# OttoPi06a-RPi3AHAT.net
KiCad netlist of a schematic drawn in EAGLE
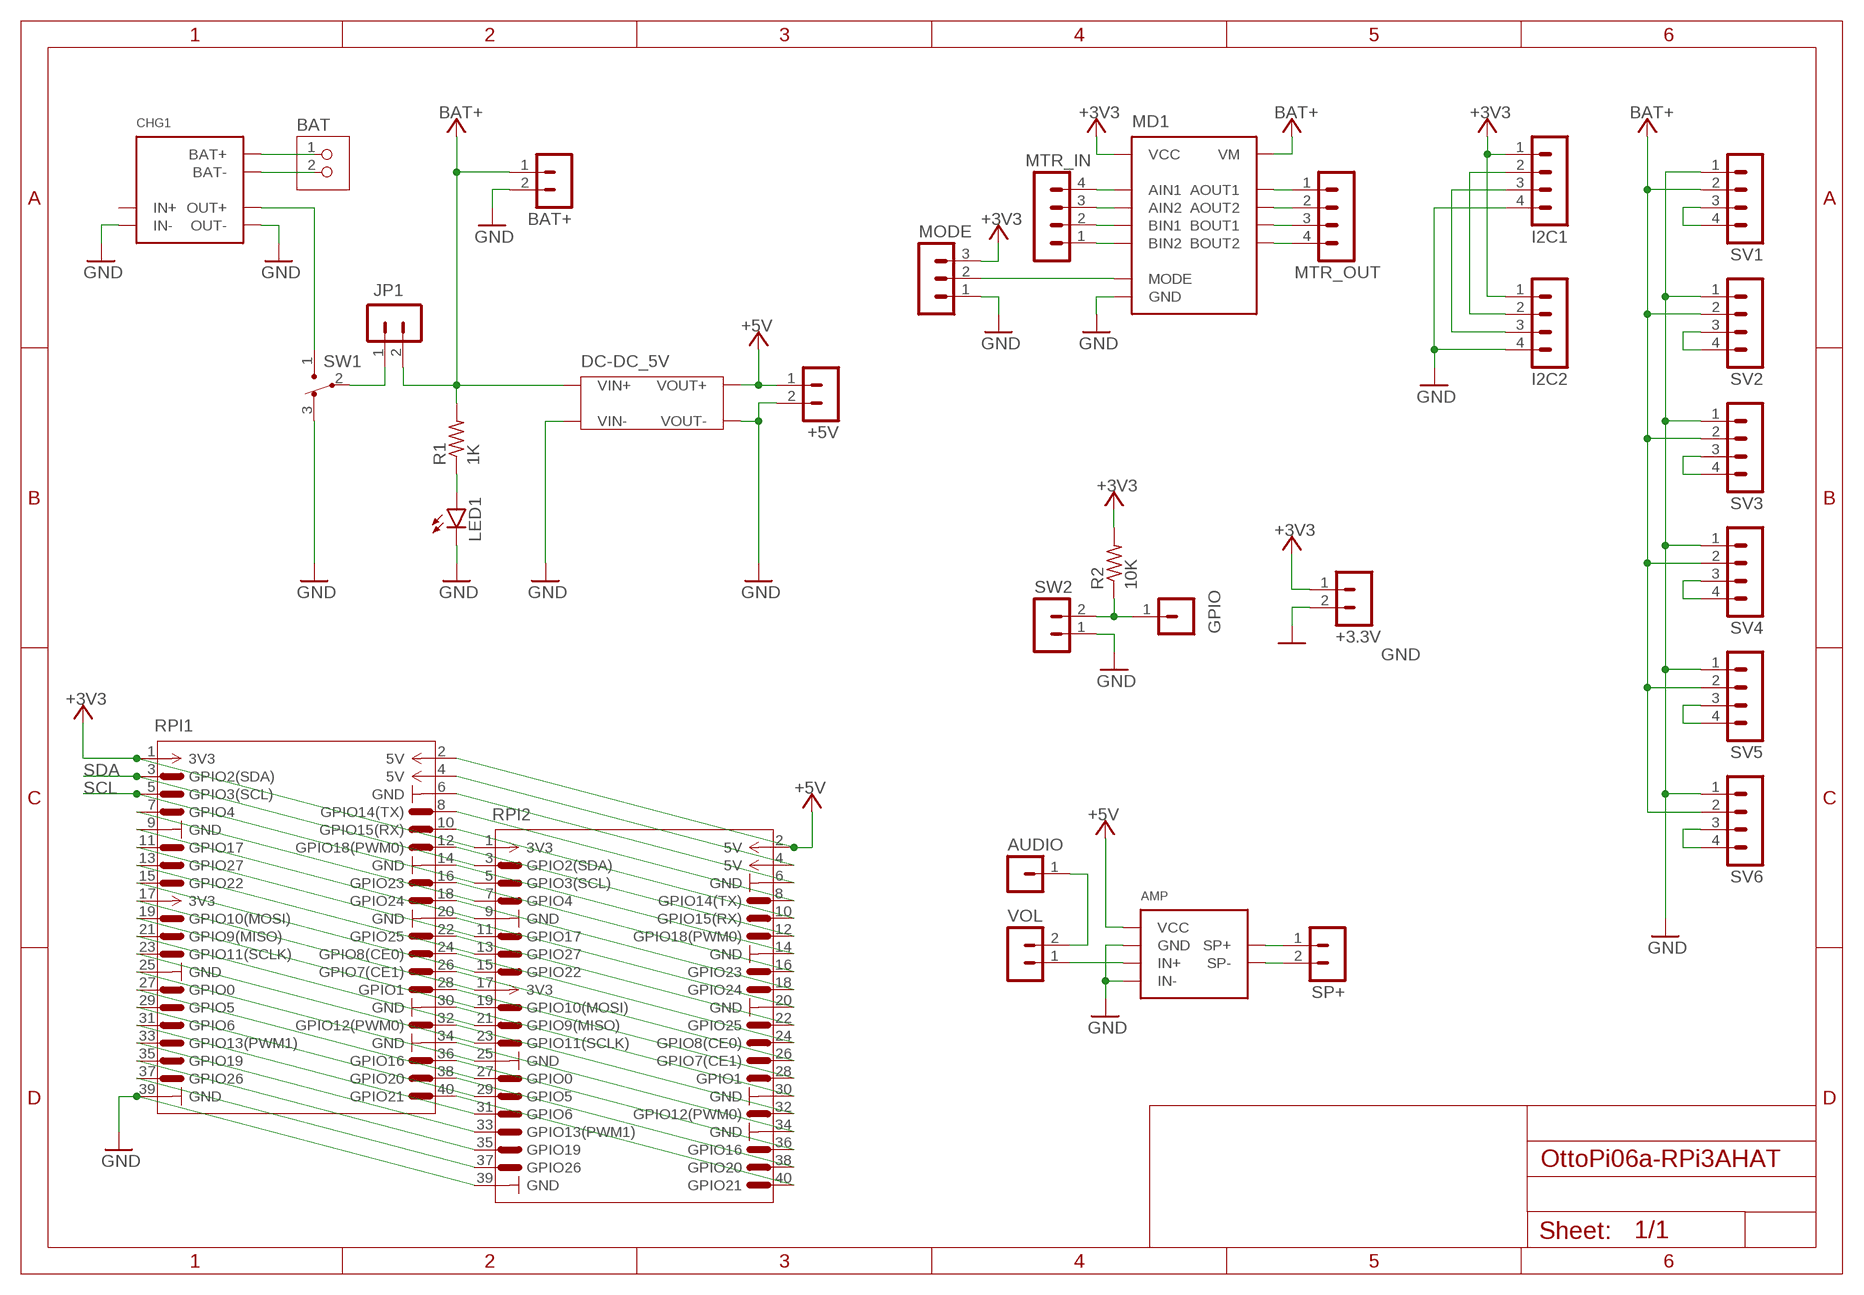
[diagram p0: schematic, sheet 1]

(export (version "E")
  (design (tool "Eeschema 10.0.6"))
  (components
    (comp (ref "+3.3V")
      (value "MA02-1")
      (footprint "eagle-import:MA02-1")
      (libsource (lib "eagle-import") (part "MA02-1"))
    )
    (comp (ref "+5V")
      (value "MA02-1")
      (footprint "eagle-import:MA02-1")
      (libsource (lib "eagle-import") (part "MA02-1"))
    )
    (comp (ref "AMP")
      (value "PAM8012MOD")
      (footprint "eagle-import:PAM8012MOD-A")
      (libsource (lib "eagle-import") (part "PAM8012MOD"))
    )
    (comp (ref "AUDIO")
      (value "MA01-1")
      (footprint "eagle-import:MA01-1")
      (libsource (lib "eagle-import") (part "MA01-1"))
    )
    (comp (ref "BAT")
      (value "JST-PH2")
      (footprint "eagle-import:JST-PH2")
      (libsource (lib "eagle-import") (part "JST-PH2"))
    )
    (comp (ref "BAT+")
      (value "MA02-1")
      (footprint "eagle-import:MA02-1")
      (libsource (lib "eagle-import") (part "MA02-1"))
    )
    (comp (ref "CHG1")
      (value "TP4056MOD1")
      (footprint "eagle-import:TP4056MOD1")
      (libsource (lib "eagle-import") (part "TP4056MOD1"))
    )
    (comp (ref "DC-DC_5V")
      (value "DCDC-5V_28V-2A")
      (footprint "eagle-import:DCDC-5V_28V-2A")
      (libsource (lib "eagle-import") (part "DCDC-5V_28V-2A"))
    )
    (comp (ref "GPIO")
      (value "MA01-1")
      (footprint "eagle-import:MA01-1")
      (libsource (lib "eagle-import") (part "MA01-1"))
    )
    (comp (ref "I2C1")
      (value "MA04-1")
      (footprint "eagle-import:MA04-1")
      (libsource (lib "eagle-import") (part "MA04-1"))
    )
    (comp (ref "I2C2")
      (value "MA04-1")
      (footprint "eagle-import:MA04-1")
      (libsource (lib "eagle-import") (part "MA04-1"))
    )
    (comp (ref "JP1")
      (value "MA02-1")
      (footprint "eagle-import:MA02-1")
      (libsource (lib "eagle-import") (part "MA02-1"))
    )
    (comp (ref "LED1")
      (value "LED3MM")
      (footprint "eagle-import:LED3MM")
      (libsource (lib "eagle-import") (part "LED3MM"))
    )
    (comp (ref "MD1")
      (value "DRV8835MOD")
      (footprint "eagle-import:DRV8835MOD")
      (libsource (lib "eagle-import") (part "DRV8835MOD"))
    )
    (comp (ref "MODE")
      (value "MA03-1")
      (footprint "eagle-import:MA03-1")
      (libsource (lib "eagle-import") (part "MA03-1"))
    )
    (comp (ref "MTR_IN")
      (value "MA04-1")
      (footprint "eagle-import:MA04-1")
      (libsource (lib "eagle-import") (part "MA04-1"))
    )
    (comp (ref "MTR_OUT")
      (value "MA04-1")
      (footprint "eagle-import:MA04-1")
      (libsource (lib "eagle-import") (part "MA04-1"))
    )
    (comp (ref "R1")
      (value "1K")
      (footprint "eagle-import:0204_7")
      (libsource (lib "eagle-import") (part "R-US_0204/7"))
    )
    (comp (ref "R2")
      (value "10K")
      (footprint "eagle-import:0204_7")
      (libsource (lib "eagle-import") (part "R-US_0204/7"))
    )
    (comp (ref "RPI1")
      (value "RPI-PIN")
      (footprint "eagle-import:RPI-PIN")
      (libsource (lib "eagle-import") (part "RPI-PIN"))
    )
    (comp (ref "RPI2")
      (value "RPI-PIN")
      (footprint "eagle-import:RPI-PIN")
      (libsource (lib "eagle-import") (part "RPI-PIN"))
    )
    (comp (ref "SP+")
      (value "MA02-1")
      (footprint "eagle-import:MA02-1")
      (libsource (lib "eagle-import") (part "MA02-1"))
    )
    (comp (ref "SV1")
      (value "MA04-1")
      (footprint "eagle-import:MA04-1")
      (libsource (lib "eagle-import") (part "MA04-1"))
    )
    (comp (ref "SV2")
      (value "MA04-1")
      (footprint "eagle-import:MA04-1")
      (libsource (lib "eagle-import") (part "MA04-1"))
    )
    (comp (ref "SV3")
      (value "MA04-1")
      (footprint "eagle-import:MA04-1")
      (libsource (lib "eagle-import") (part "MA04-1"))
    )
    (comp (ref "SV4")
      (value "MA04-1")
      (footprint "eagle-import:MA04-1")
      (libsource (lib "eagle-import") (part "MA04-1"))
    )
    (comp (ref "SV5")
      (value "MA04-1")
      (footprint "eagle-import:MA04-1")
      (libsource (lib "eagle-import") (part "MA04-1"))
    )
    (comp (ref "SV6")
      (value "MA04-1")
      (footprint "eagle-import:MA04-1")
      (libsource (lib "eagle-import") (part "MA04-1"))
    )
    (comp (ref "SW1")
      (value "SW3-1")
      (footprint "eagle-import:SW3-1")
      (fields (field (name "MF") "HiLetgo"))
      (libsource (lib "eagle-import") (part "SW3-1"))
    )
    (comp (ref "SW2")
      (value "MA02-1")
      (footprint "eagle-import:MA02-1")
      (libsource (lib "eagle-import") (part "MA02-1"))
    )
    (comp (ref "VOL")
      (value "MA02-1")
      (footprint "eagle-import:MA02-1")
      (libsource (lib "eagle-import") (part "MA02-1"))
    )
  )
  (nets
    (net (code "1") (name "+3V3") (class "Default")
      (node (ref "+3.3V") (pin "1") (pinfunction "1_1") (pintype "passive"))
      (node (ref "I2C1") (pin "1") (pinfunction "1_1") (pintype "passive"))
      (node (ref "I2C2") (pin "1") (pinfunction "1_1") (pintype "passive"))
      (node (ref "MD1") (pin "VCC") (pinfunction "VCC_VCC") (pintype "input"))
      (node (ref "MODE") (pin "3") (pinfunction "3_3") (pintype "passive"))
      (node (ref "R2") (pin "2") (pinfunction "2_2") (pintype "passive"))
      (node (ref "RPI1") (pin "1") (pinfunction "3V3_1") (pintype "passive"))
      (node (ref "RPI2") (pin "1") (pinfunction "3V3_1") (pintype "passive"))
    )
    (net (code "2") (name "+5V") (class "Default")
      (node (ref "+5V") (pin "1") (pinfunction "1_1") (pintype "passive"))
      (node (ref "AMP") (pin "V+") (pinfunction "VCC_V+") (pintype "passive"))
      (node (ref "DC-DC_5V") (pin "VOUT+") (pinfunction "VOUT+_VOUT+") (pintype "power_in"))
      (node (ref "RPI1") (pin "2") (pinfunction "5V_2") (pintype "passive"))
      (node (ref "RPI2") (pin "2") (pinfunction "5V_2") (pintype "passive"))
    )
    (net (code "3") (name "/SCL") (class "Default")
      (node (ref "I2C1") (pin "3") (pinfunction "3_3") (pintype "passive"))
      (node (ref "I2C2") (pin "3") (pinfunction "3_3") (pintype "passive"))
      (node (ref "RPI1") (pin "5") (pinfunction "GPIO3(SCL)_5") (pintype "passive"))
      (node (ref "RPI2") (pin "5") (pinfunction "GPIO3(SCL)_5") (pintype "passive"))
    )
    (net (code "4") (name "/SDA") (class "Default")
      (node (ref "I2C1") (pin "2") (pinfunction "2_2") (pintype "passive"))
      (node (ref "I2C2") (pin "2") (pinfunction "2_2") (pintype "passive"))
      (node (ref "RPI1") (pin "3") (pinfunction "GPIO2(SDA)_3") (pintype "passive"))
      (node (ref "RPI2") (pin "3") (pinfunction "GPIO2(SDA)_3") (pintype "passive"))
    )
    (net (code "5") (name "BAT+") (class "Default")
      (node (ref "BAT+") (pin "1") (pinfunction "1_1") (pintype "passive"))
      (node (ref "DC-DC_5V") (pin "VIN+") (pinfunction "VIN+_VIN+") (pintype "power_in"))
      (node (ref "JP1") (pin "2") (pinfunction "2_2") (pintype "passive"))
      (node (ref "MD1") (pin "VM") (pinfunction "VM_VM") (pintype "input"))
      (node (ref "R1") (pin "2") (pinfunction "2_2") (pintype "passive"))
      (node (ref "SV1") (pin "2") (pinfunction "2_2") (pintype "passive"))
      (node (ref "SV2") (pin "2") (pinfunction "2_2") (pintype "passive"))
      (node (ref "SV3") (pin "2") (pinfunction "2_2") (pintype "passive"))
      (node (ref "SV4") (pin "2") (pinfunction "2_2") (pintype "passive"))
      (node (ref "SV5") (pin "2") (pinfunction "2_2") (pintype "passive"))
      (node (ref "SV6") (pin "2") (pinfunction "2_2") (pintype "passive"))
    )
    (net (code "6") (name "GND") (class "Default")
      (node (ref "+3.3V") (pin "2") (pinfunction "2_2") (pintype "passive"))
      (node (ref "+5V") (pin "2") (pinfunction "2_2") (pintype "passive"))
      (node (ref "AMP") (pin "GND") (pinfunction "GND_GND") (pintype "passive"))
      (node (ref "AMP") (pin "IN-") (pinfunction "IN-_IN-") (pintype "input"))
      (node (ref "BAT+") (pin "2") (pinfunction "2_2") (pintype "passive"))
      (node (ref "CHG1") (pin "IN-") (pinfunction "IN-_IN-") (pintype "passive"))
      (node (ref "CHG1") (pin "OUT-") (pinfunction "OUT-_OUT-") (pintype "passive"))
      (node (ref "DC-DC_5V") (pin "VIN-") (pinfunction "VIN-_VIN-") (pintype "power_in"))
      (node (ref "DC-DC_5V") (pin "VOUT-") (pinfunction "VOUT-_VOUT-") (pintype "power_in"))
      (node (ref "I2C1") (pin "4") (pinfunction "4_4") (pintype "passive"))
      (node (ref "I2C2") (pin "4") (pinfunction "4_4") (pintype "passive"))
      (node (ref "LED1") (pin "K") (pinfunction "C_K") (pintype "passive"))
      (node (ref "MD1") (pin "GND") (pinfunction "GND_GND") (pintype "power_in"))
      (node (ref "MODE") (pin "1") (pinfunction "1_1") (pintype "passive"))
      (node (ref "RPI1") (pin "39") (pinfunction "GND_39") (pintype "passive"))
      (node (ref "RPI2") (pin "39") (pinfunction "GND_39") (pintype "passive"))
      (node (ref "SV1") (pin "1") (pinfunction "1_1") (pintype "passive"))
      (node (ref "SV2") (pin "1") (pinfunction "1_1") (pintype "passive"))
      (node (ref "SV3") (pin "1") (pinfunction "1_1") (pintype "passive"))
      (node (ref "SV4") (pin "1") (pinfunction "1_1") (pintype "passive"))
      (node (ref "SV5") (pin "1") (pinfunction "1_1") (pintype "passive"))
      (node (ref "SV6") (pin "1") (pinfunction "1_1") (pintype "passive"))
      (node (ref "SW1") (pin "3") (pinfunction "3_3") (pintype "passive"))
      (node (ref "SW2") (pin "1") (pinfunction "1_1") (pintype "passive"))
    )
    (net (code "7") (name "Net-(AMP-PadIN+)") (class "Default")
      (node (ref "AMP") (pin "IN+") (pinfunction "IN+_IN+") (pintype "input"))
      (node (ref "VOL") (pin "1") (pinfunction "1_1") (pintype "passive"))
    )
    (net (code "8") (name "Net-(AMP-SP+)") (class "Default")
      (node (ref "AMP") (pin "SP+@1") (pinfunction "SP+_SP+@1") (pintype "output"))
      (node (ref "SP+") (pin "1") (pinfunction "1_1") (pintype "passive"))
    )
    (net (code "9") (name "Net-(AMP-SP-)") (class "Default")
      (node (ref "AMP") (pin "SP-@1") (pinfunction "SP-_SP-@1") (pintype "output"))
      (node (ref "SP+") (pin "2") (pinfunction "2_2") (pintype "passive"))
    )
    (net (code "10") (name "Net-(AUDIO-Pad1)") (class "Default")
      (node (ref "AUDIO") (pin "1") (pinfunction "1_1") (pintype "passive"))
      (node (ref "VOL") (pin "2") (pinfunction "2_2") (pintype "passive"))
    )
    (net (code "11") (name "Net-(BAT-Pad1)") (class "Default")
      (node (ref "BAT") (pin "1") (pinfunction "1_1") (pintype "passive"))
      (node (ref "CHG1") (pin "BAT+") (pinfunction "BAT+_BAT+") (pintype "passive"))
    )
    (net (code "12") (name "Net-(BAT-Pad2)") (class "Default")
      (node (ref "BAT") (pin "2") (pinfunction "2_2") (pintype "passive"))
      (node (ref "CHG1") (pin "BAT-") (pinfunction "BAT-_BAT-") (pintype "passive"))
    )
    (net (code "13") (name "Net-(CHG1-PadOUT+)") (class "Default")
      (node (ref "CHG1") (pin "OUT+") (pinfunction "OUT+_OUT+") (pintype "passive"))
      (node (ref "SW1") (pin "1") (pinfunction "1_1") (pintype "passive"))
    )
    (net (code "14") (name "Net-(GPIO-Pad1)") (class "Default")
      (node (ref "GPIO") (pin "1") (pinfunction "1_1") (pintype "passive"))
      (node (ref "R2") (pin "1") (pinfunction "1_1") (pintype "passive"))
      (node (ref "SW2") (pin "2") (pinfunction "2_2") (pintype "passive"))
    )
    (net (code "15") (name "Net-(JP1-Pad1)") (class "Default")
      (node (ref "JP1") (pin "1") (pinfunction "1_1") (pintype "passive"))
      (node (ref "SW1") (pin "2") (pinfunction "2_2") (pintype "passive"))
    )
    (net (code "16") (name "Net-(LED1-PadA)") (class "Default")
      (node (ref "LED1") (pin "A") (pinfunction "A_A") (pintype "passive"))
      (node (ref "R1") (pin "1") (pinfunction "1_1") (pintype "passive"))
    )
    (net (code "17") (name "Net-(MD1-PadAIN1)") (class "Default")
      (node (ref "MD1") (pin "AIN1") (pinfunction "AIN1_AIN1") (pintype "input"))
      (node (ref "MTR_IN") (pin "4") (pinfunction "4_4") (pintype "passive"))
    )
    (net (code "18") (name "Net-(MD1-PadAIN2)") (class "Default")
      (node (ref "MD1") (pin "AIN2") (pinfunction "AIN2_AIN2") (pintype "input"))
      (node (ref "MTR_IN") (pin "3") (pinfunction "3_3") (pintype "passive"))
    )
    (net (code "19") (name "Net-(MD1-PadAOUT1)") (class "Default")
      (node (ref "MD1") (pin "AOUT1") (pinfunction "AOUT1_AOUT1") (pintype "output"))
      (node (ref "MTR_OUT") (pin "1") (pinfunction "1_1") (pintype "passive"))
    )
    (net (code "20") (name "Net-(MD1-PadAOUT2)") (class "Default")
      (node (ref "MD1") (pin "AOUT2") (pinfunction "AOUT2_AOUT2") (pintype "output"))
      (node (ref "MTR_OUT") (pin "2") (pinfunction "2_2") (pintype "passive"))
    )
    (net (code "21") (name "Net-(MD1-PadBIN1)") (class "Default")
      (node (ref "MD1") (pin "BIN1") (pinfunction "BIN1_BIN1") (pintype "input"))
      (node (ref "MTR_IN") (pin "2") (pinfunction "2_2") (pintype "passive"))
    )
    (net (code "22") (name "Net-(MD1-PadBIN2)") (class "Default")
      (node (ref "MD1") (pin "BIN2") (pinfunction "BIN2_BIN2") (pintype "input"))
      (node (ref "MTR_IN") (pin "1") (pinfunction "1_1") (pintype "passive"))
    )
    (net (code "23") (name "Net-(MD1-PadBOUT1)") (class "Default")
      (node (ref "MD1") (pin "BOUT1") (pinfunction "BOUT1_BOUT1") (pintype "output"))
      (node (ref "MTR_OUT") (pin "3") (pinfunction "3_3") (pintype "passive"))
    )
    (net (code "24") (name "Net-(MD1-PadBOUT2)") (class "Default")
      (node (ref "MD1") (pin "BOUT2") (pinfunction "BOUT2_BOUT2") (pintype "output"))
      (node (ref "MTR_OUT") (pin "4") (pinfunction "4_4") (pintype "passive"))
    )
    (net (code "25") (name "Net-(MD1-PadMODE)") (class "Default")
      (node (ref "MD1") (pin "MODE") (pinfunction "MODE_MODE") (pintype "input"))
      (node (ref "MODE") (pin "2") (pinfunction "2_2") (pintype "passive"))
    )
    (net (code "26") (name "Net-(RPI1-3V3-Pad17)") (class "Default")
      (node (ref "RPI1") (pin "17") (pinfunction "3V3_17") (pintype "passive"))
      (node (ref "RPI2") (pin "17") (pinfunction "3V3_17") (pintype "passive"))
    )
    (net (code "27") (name "Net-(RPI1-5V-Pad4)") (class "Default")
      (node (ref "RPI1") (pin "4") (pinfunction "5V_4") (pintype "passive"))
      (node (ref "RPI2") (pin "4") (pinfunction "5V_4") (pintype "passive"))
    )
    (net (code "28") (name "Net-(RPI1-GND-Pad6)") (class "Default")
      (node (ref "RPI1") (pin "6") (pinfunction "GND_6") (pintype "passive"))
      (node (ref "RPI2") (pin "6") (pinfunction "GND_6") (pintype "passive"))
    )
    (net (code "29") (name "Net-(RPI1-GND-Pad9)") (class "Default")
      (node (ref "RPI1") (pin "9") (pinfunction "GND_9") (pintype "passive"))
      (node (ref "RPI2") (pin "9") (pinfunction "GND_9") (pintype "passive"))
    )
    (net (code "30") (name "Net-(RPI1-GND-Pad14)") (class "Default")
      (node (ref "RPI1") (pin "14") (pinfunction "GND_14") (pintype "passive"))
      (node (ref "RPI2") (pin "14") (pinfunction "GND_14") (pintype "passive"))
    )
    (net (code "31") (name "Net-(RPI1-GND-Pad20)") (class "Default")
      (node (ref "RPI1") (pin "20") (pinfunction "GND_20") (pintype "passive"))
      (node (ref "RPI2") (pin "20") (pinfunction "GND_20") (pintype "passive"))
    )
    (net (code "32") (name "Net-(RPI1-GND-Pad25)") (class "Default")
      (node (ref "RPI1") (pin "25") (pinfunction "GND_25") (pintype "passive"))
      (node (ref "RPI2") (pin "25") (pinfunction "GND_25") (pintype "passive"))
    )
    (net (code "33") (name "Net-(RPI1-GND-Pad30)") (class "Default")
      (node (ref "RPI1") (pin "30") (pinfunction "GND_30") (pintype "passive"))
      (node (ref "RPI2") (pin "30") (pinfunction "GND_30") (pintype "passive"))
    )
    (net (code "34") (name "Net-(RPI1-GND-Pad34)") (class "Default")
      (node (ref "RPI1") (pin "34") (pinfunction "GND_34") (pintype "passive"))
      (node (ref "RPI2") (pin "34") (pinfunction "GND_34") (pintype "passive"))
    )
    (net (code "35") (name "Net-(RPI1-GPIO0)") (class "Default")
      (node (ref "RPI1") (pin "27") (pinfunction "GPIO0_27") (pintype "passive"))
      (node (ref "RPI2") (pin "27") (pinfunction "GPIO0_27") (pintype "passive"))
    )
    (net (code "36") (name "Net-(RPI1-GPIO1)") (class "Default")
      (node (ref "RPI1") (pin "28") (pinfunction "GPIO1_28") (pintype "passive"))
      (node (ref "RPI2") (pin "28") (pinfunction "GPIO1_28") (pintype "passive"))
    )
    (net (code "37") (name "Net-(RPI1-GPIO4)") (class "Default")
      (node (ref "RPI1") (pin "7") (pinfunction "GPIO4_7") (pintype "passive"))
      (node (ref "RPI2") (pin "7") (pinfunction "GPIO4_7") (pintype "passive"))
    )
    (net (code "38") (name "Net-(RPI1-GPIO5)") (class "Default")
      (node (ref "RPI1") (pin "29") (pinfunction "GPIO5_29") (pintype "passive"))
      (node (ref "RPI2") (pin "29") (pinfunction "GPIO5_29") (pintype "passive"))
    )
    (net (code "39") (name "Net-(RPI1-GPIO6)") (class "Default")
      (node (ref "RPI1") (pin "31") (pinfunction "GPIO6_31") (pintype "passive"))
      (node (ref "RPI2") (pin "31") (pinfunction "GPIO6_31") (pintype "passive"))
    )
    (net (code "40") (name "Net-(RPI1-GPIO7(CE1))") (class "Default")
      (node (ref "RPI1") (pin "26") (pinfunction "GPIO7(CE1)_26") (pintype "passive"))
      (node (ref "RPI2") (pin "26") (pinfunction "GPIO7(CE1)_26") (pintype "passive"))
    )
    (net (code "41") (name "Net-(RPI1-GPIO8(CE0))") (class "Default")
      (node (ref "RPI1") (pin "24") (pinfunction "GPIO8(CE0)_24") (pintype "passive"))
      (node (ref "RPI2") (pin "24") (pinfunction "GPIO8(CE0)_24") (pintype "passive"))
    )
    (net (code "42") (name "Net-(RPI1-GPIO9(MISO))") (class "Default")
      (node (ref "RPI1") (pin "21") (pinfunction "GPIO9(MISO)_21") (pintype "passive"))
      (node (ref "RPI2") (pin "21") (pinfunction "GPIO9(MISO)_21") (pintype "passive"))
    )
    (net (code "43") (name "Net-(RPI1-GPIO10(MOSI))") (class "Default")
      (node (ref "RPI1") (pin "19") (pinfunction "GPIO10(MOSI)_19") (pintype "passive"))
      (node (ref "RPI2") (pin "19") (pinfunction "GPIO10(MOSI)_19") (pintype "passive"))
    )
    (net (code "44") (name "Net-(RPI1-GPIO11(SCLK))") (class "Default")
      (node (ref "RPI1") (pin "23") (pinfunction "GPIO11(SCLK)_23") (pintype "passive"))
      (node (ref "RPI2") (pin "23") (pinfunction "GPIO11(SCLK)_23") (pintype "passive"))
    )
    (net (code "45") (name "Net-(RPI1-GPIO12(PWM0))") (class "Default")
      (node (ref "RPI1") (pin "32") (pinfunction "GPIO12(PWM0)_32") (pintype "passive"))
      (node (ref "RPI2") (pin "32") (pinfunction "GPIO12(PWM0)_32") (pintype "passive"))
    )
    (net (code "46") (name "Net-(RPI1-GPIO13(PWM1))") (class "Default")
      (node (ref "RPI1") (pin "33") (pinfunction "GPIO13(PWM1)_33") (pintype "passive"))
      (node (ref "RPI2") (pin "33") (pinfunction "GPIO13(PWM1)_33") (pintype "passive"))
    )
    (net (code "47") (name "Net-(RPI1-GPIO14(TX))") (class "Default")
      (node (ref "RPI1") (pin "8") (pinfunction "GPIO14(TX)_8") (pintype "passive"))
      (node (ref "RPI2") (pin "8") (pinfunction "GPIO14(TX)_8") (pintype "passive"))
    )
    (net (code "48") (name "Net-(RPI1-GPIO15(RX))") (class "Default")
      (node (ref "RPI1") (pin "10") (pinfunction "GPIO15(RX)_10") (pintype "passive"))
      (node (ref "RPI2") (pin "10") (pinfunction "GPIO15(RX)_10") (pintype "passive"))
    )
    (net (code "49") (name "Net-(RPI1-GPIO16)") (class "Default")
      (node (ref "RPI1") (pin "36") (pinfunction "GPIO16_36") (pintype "passive"))
      (node (ref "RPI2") (pin "36") (pinfunction "GPIO16_36") (pintype "passive"))
    )
    (net (code "50") (name "Net-(RPI1-GPIO17)") (class "Default")
      (node (ref "RPI1") (pin "11") (pinfunction "GPIO17_11") (pintype "passive"))
      (node (ref "RPI2") (pin "11") (pinfunction "GPIO17_11") (pintype "passive"))
    )
    (net (code "51") (name "Net-(RPI1-GPIO18(PWM0))") (class "Default")
      (node (ref "RPI1") (pin "12") (pinfunction "GPIO18(PWM0)_12") (pintype "passive"))
      (node (ref "RPI2") (pin "12") (pinfunction "GPIO18(PWM0)_12") (pintype "passive"))
    )
    (net (code "52") (name "Net-(RPI1-GPIO19)") (class "Default")
      (node (ref "RPI1") (pin "35") (pinfunction "GPIO19_35") (pintype "passive"))
      (node (ref "RPI2") (pin "35") (pinfunction "GPIO19_35") (pintype "passive"))
    )
    (net (code "53") (name "Net-(RPI1-GPIO20)") (class "Default")
      (node (ref "RPI1") (pin "38") (pinfunction "GPIO20_38") (pintype "passive"))
      (node (ref "RPI2") (pin "38") (pinfunction "GPIO20_38") (pintype "passive"))
    )
    (net (code "54") (name "Net-(RPI1-GPIO21)") (class "Default")
      (node (ref "RPI1") (pin "40") (pinfunction "GPIO21_40") (pintype "passive"))
      (node (ref "RPI2") (pin "40") (pinfunction "GPIO21_40") (pintype "passive"))
    )
    (net (code "55") (name "Net-(RPI1-GPIO22)") (class "Default")
      (node (ref "RPI1") (pin "15") (pinfunction "GPIO22_15") (pintype "passive"))
      (node (ref "RPI2") (pin "15") (pinfunction "GPIO22_15") (pintype "passive"))
    )
    (net (code "56") (name "Net-(RPI1-GPIO23)") (class "Default")
      (node (ref "RPI1") (pin "16") (pinfunction "GPIO23_16") (pintype "passive"))
      (node (ref "RPI2") (pin "16") (pinfunction "GPIO23_16") (pintype "passive"))
    )
    (net (code "57") (name "Net-(RPI1-GPIO24)") (class "Default")
      (node (ref "RPI1") (pin "18") (pinfunction "GPIO24_18") (pintype "passive"))
      (node (ref "RPI2") (pin "18") (pinfunction "GPIO24_18") (pintype "passive"))
    )
    (net (code "58") (name "Net-(RPI1-GPIO25)") (class "Default")
      (node (ref "RPI1") (pin "22") (pinfunction "GPIO25_22") (pintype "passive"))
      (node (ref "RPI2") (pin "22") (pinfunction "GPIO25_22") (pintype "passive"))
    )
    (net (code "59") (name "Net-(RPI1-GPIO26)") (class "Default")
      (node (ref "RPI1") (pin "37") (pinfunction "GPIO26_37") (pintype "passive"))
      (node (ref "RPI2") (pin "37") (pinfunction "GPIO26_37") (pintype "passive"))
    )
    (net (code "60") (name "Net-(RPI1-GPIO27)") (class "Default")
      (node (ref "RPI1") (pin "13") (pinfunction "GPIO27_13") (pintype "passive"))
      (node (ref "RPI2") (pin "13") (pinfunction "GPIO27_13") (pintype "passive"))
    )
    (net (code "61") (name "Net-(SV1-Pad3)") (class "Default")
      (node (ref "SV1") (pin "3") (pinfunction "3_3") (pintype "passive"))
      (node (ref "SV1") (pin "4") (pinfunction "4_4") (pintype "passive"))
    )
    (net (code "62") (name "Net-(SV2-Pad3)") (class "Default")
      (node (ref "SV2") (pin "3") (pinfunction "3_3") (pintype "passive"))
      (node (ref "SV2") (pin "4") (pinfunction "4_4") (pintype "passive"))
    )
    (net (code "63") (name "Net-(SV3-Pad3)") (class "Default")
      (node (ref "SV3") (pin "3") (pinfunction "3_3") (pintype "passive"))
      (node (ref "SV3") (pin "4") (pinfunction "4_4") (pintype "passive"))
    )
    (net (code "64") (name "Net-(SV4-Pad3)") (class "Default")
      (node (ref "SV4") (pin "3") (pinfunction "3_3") (pintype "passive"))
      (node (ref "SV4") (pin "4") (pinfunction "4_4") (pintype "passive"))
    )
    (net (code "65") (name "Net-(SV5-Pad3)") (class "Default")
      (node (ref "SV5") (pin "3") (pinfunction "3_3") (pintype "passive"))
      (node (ref "SV5") (pin "4") (pinfunction "4_4") (pintype "passive"))
    )
    (net (code "66") (name "Net-(SV6-Pad3)") (class "Default")
      (node (ref "SV6") (pin "3") (pinfunction "3_3") (pintype "passive"))
      (node (ref "SV6") (pin "4") (pinfunction "4_4") (pintype "passive"))
    )
    (net (code "67") (name "unconnected-(CHG1-PadIN+)") (class "Default")
      (node (ref "CHG1") (pin "IN+") (pinfunction "IN+_IN+") (pintype "passive"))
    )
  )
)
